# FM25V20A_base.net
KiCad netlist of a schematic drawn in Altium Designer
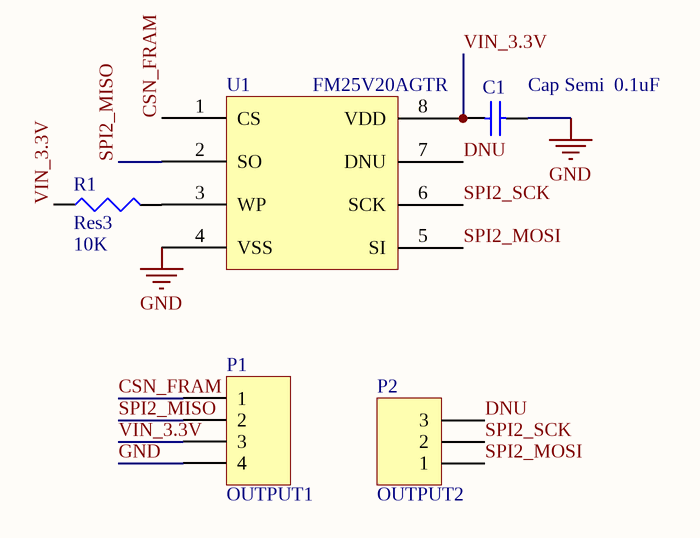
[diagram p0: FM25V20A_base.SchDoc]

(export (version "E")
  (design (tool "Eeschema 10.0.6"))
  (components
    (comp (ref "C1")
      (value "Cap Semi")
      (footprint "1608[0603]")
      (description "Capacitor (Semiconductor SIM Model)")
      (fields (field (name "ALTIUM_VALUE") "0.1uF") (field (name "PUBLISHER") "Altium Limited"))
      (libsource (lib "Miscellaneous Devices") (part "Cap Semi"))
    )
    (comp (ref "P1")
      (value "OUTPUT1")
      (footprint "HDR1X4")
      (description "Header, 4-Pin")
      (fields (field (name "PUBLISHER") "Altium Limited"))
      (libsource (lib "Miscellaneous Connectors") (part "Header 4"))
    )
    (comp (ref "P2")
      (value "OUTPUT2")
      (footprint "HDR1X3")
      (description "Header, 3-Pin")
      (fields (field (name "PUBLISHER") "Altium Limited"))
      (libsource (lib "Miscellaneous Connectors") (part "Header 3"))
    )
    (comp (ref "R1")
      (value "Res3")
      (footprint "J1-0603")
      (description "Resistor")
      (fields (field (name "ALTIUM_VALUE") "10K") (field (name "PUBLISHER") "Altium Limited"))
      (libsource (lib "Miscellaneous Devices") (part "Res3"))
    )
    (comp (ref "U1")
      (value "FM25V20AGTR")
      (footprint "SOIC-8N")
      (libsource (lib "Components_myself") (part "FM25V20AGTR"))
    )
  )
  (nets
    (net (code "1") (name "/CSN_FRAM") (class "Default")
      (node (ref "P1") (pin "1") (pinfunction "1_1") (pintype "passive"))
      (node (ref "U1") (pin "1") (pinfunction "CS_1") (pintype "passive"))
    )
    (net (code "2") (name "/DNU") (class "Default")
      (node (ref "P2") (pin "3") (pinfunction "3_3") (pintype "passive"))
      (node (ref "U1") (pin "7") (pinfunction "DNU_7") (pintype "passive"))
    )
    (net (code "3") (name "/SPI2_MISO") (class "Default")
      (node (ref "P1") (pin "2") (pinfunction "2_2") (pintype "passive"))
      (node (ref "U1") (pin "2") (pinfunction "SO_2") (pintype "passive"))
    )
    (net (code "4") (name "/SPI2_MOSI") (class "Default")
      (node (ref "P2") (pin "1") (pinfunction "1_1") (pintype "passive"))
      (node (ref "U1") (pin "5") (pinfunction "SI_5") (pintype "passive"))
    )
    (net (code "5") (name "/SPI2_SCK") (class "Default")
      (node (ref "P2") (pin "2") (pinfunction "2_2") (pintype "passive"))
      (node (ref "U1") (pin "6") (pinfunction "SCK_6") (pintype "passive"))
    )
    (net (code "6") (name "/VIN_3.3V") (class "Default")
      (node (ref "C1") (pin "1") (pinfunction "1_1") (pintype "passive"))
      (node (ref "P1") (pin "3") (pinfunction "3_3") (pintype "passive"))
      (node (ref "R1") (pin "1") (pinfunction "1_1") (pintype "passive"))
      (node (ref "U1") (pin "8") (pinfunction "VDD_8") (pintype "passive"))
    )
    (net (code "7") (name "GND") (class "Default")
      (node (ref "C1") (pin "2") (pinfunction "2_2") (pintype "passive"))
      (node (ref "P1") (pin "4") (pinfunction "4_4") (pintype "passive"))
      (node (ref "U1") (pin "4") (pinfunction "VSS_4") (pintype "passive"))
    )
    (net (code "8") (name "Net-(U1-WP)") (class "Default")
      (node (ref "R1") (pin "2") (pinfunction "2_2") (pintype "passive"))
      (node (ref "U1") (pin "3") (pinfunction "WP_3") (pintype "passive"))
    )
  )
)
